# Edubot_v1_2.net
KiCad netlist of a schematic drawn in Altium Designer
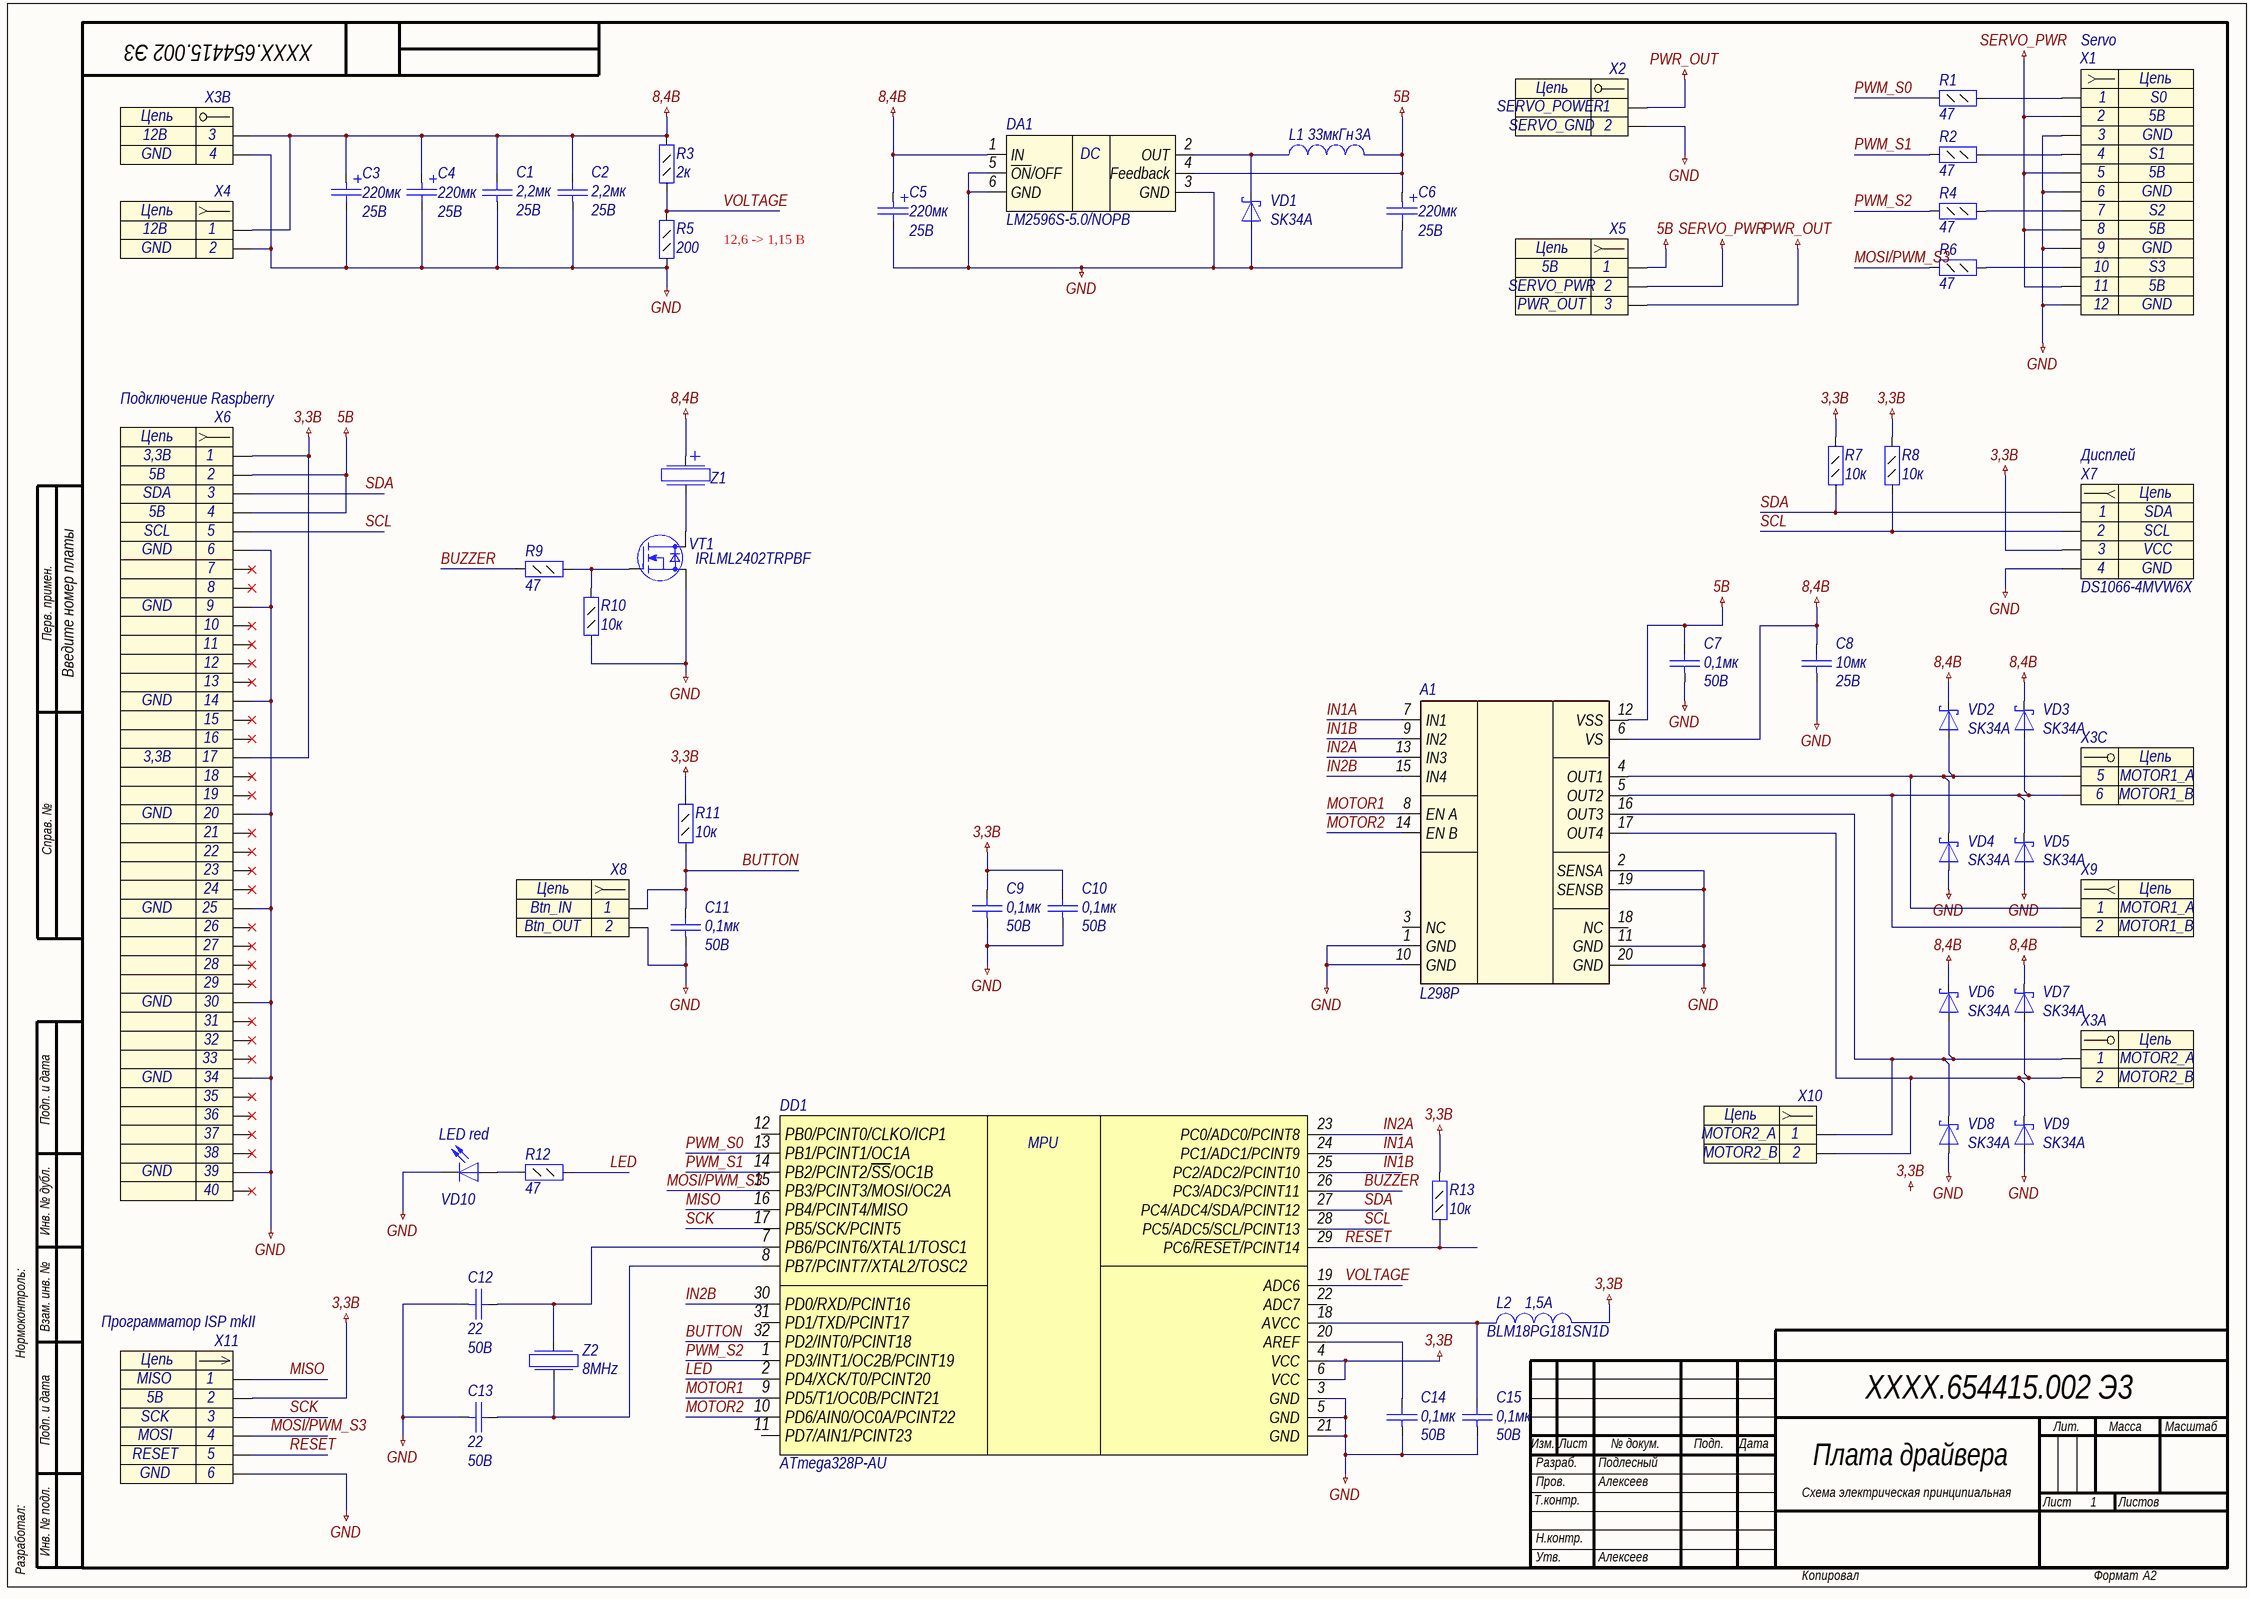
[diagram p0: Edubot v1.2.SchDoc]

(export (version "E")
  (design (tool "Eeschema 10.0.6"))
  (components
    (comp (ref "A1")
      (value "L298P")
      (footprint "POWERSO20")
      (description "FULL BRIDGE DC MOTOR DRIVER")
      (libsource (lib "MOP44") (part "L298P"))
    )
    (comp (ref "C1")
      (value "2,2мк")
      (footprint "C0805")
      (description "Конденсатор")
      (fields (field (name "VOLTAGE") "25B") (field (name "PART NUMBER") "GRM21BR71E225K"))
      (libsource (lib "MOP44") (part "Capacitor"))
    )
    (comp (ref "C2")
      (value "2,2мк")
      (footprint "C0805")
      (description "Конденсатор")
      (fields (field (name "VOLTAGE") "25B") (field (name "PART NUMBER") "GRM21BR71E225K"))
      (libsource (lib "MOP44") (part "Capacitor"))
    )
    (comp (ref "C3")
      (value "220мк")
      (footprint "Cap_SMD_radial_polar(8x10.2)")
      (description "Конденсатор полярный")
      (fields
        (field (name "VOLTAGE") "25В")
        (field (name "PART NUMBER") "JCK1E221M080105")
        (field (name "Comment") "Capacitor_pol")
      )
      (libsource (lib "MOP44") (part "Capacitor_pol"))
    )
    (comp (ref "C4")
      (value "220мк")
      (footprint "Cap_SMD_radial_polar(8x10.2)")
      (description "Конденсатор полярный")
      (fields
        (field (name "VOLTAGE") "25В")
        (field (name "PART NUMBER") "JCK1E221M080105")
        (field (name "Comment") "Capacitor_pol")
      )
      (libsource (lib "MOP44") (part "Capacitor_pol"))
    )
    (comp (ref "C5")
      (value "220мк")
      (footprint "Cap_SMD_radial_polar(8x10.2)")
      (description "Конденсатор полярный")
      (fields
        (field (name "VOLTAGE") "25В")
        (field (name "PART NUMBER") "JCK1E221M080105")
        (field (name "Comment") "Capacitor_pol")
      )
      (libsource (lib "MOP44") (part "Capacitor_pol"))
    )
    (comp (ref "C6")
      (value "220мк")
      (footprint "Cap_SMD_radial_polar(8x10.2)")
      (description "Конденсатор полярный")
      (fields
        (field (name "VOLTAGE") "25В")
        (field (name "PART NUMBER") "JCK1E221M080105")
        (field (name "Comment") "Capacitor_pol")
      )
      (libsource (lib "MOP44") (part "Capacitor_pol"))
    )
    (comp (ref "C7")
      (value "0,1мк")
      (footprint "C0805")
      (description "Конденсатор")
      (fields (field (name "VOLTAGE") "50В") (field (name "PART NUMBER") "GRM21BR71H104KA01L "))
      (libsource (lib "MOP44") (part "Capacitor"))
    )
    (comp (ref "C8")
      (value "10мк")
      (footprint "C1210")
      (description "Конденсатор")
      (fields (field (name "VOLTAGE") "25В") (field (name "PART NUMBER") "GRM32ER61A106K"))
      (libsource (lib "MOP44") (part "Capacitor"))
    )
    (comp (ref "C9")
      (value "0,1мк")
      (footprint "C0805")
      (description "Конденсатор")
      (fields (field (name "VOLTAGE") "50В") (field (name "PART NUMBER") "GRM21BR71H104KA01L "))
      (libsource (lib "MOP44") (part "Capacitor"))
    )
    (comp (ref "C10")
      (value "0,1мк")
      (footprint "C0805")
      (description "Конденсатор")
      (fields (field (name "VOLTAGE") "50В") (field (name "PART NUMBER") "GRM21BR71H104KA01L "))
      (libsource (lib "MOP44") (part "Capacitor"))
    )
    (comp (ref "C11")
      (value "0,1мк")
      (footprint "C0805")
      (description "Конденсатор")
      (fields (field (name "VOLTAGE") "50В") (field (name "PART NUMBER") "GRM21BR71H104KA01L "))
      (libsource (lib "MOP44") (part "Capacitor"))
    )
    (comp (ref "C12")
      (value "22")
      (footprint "C0805")
      (description "Конденсатор")
      (fields (field (name "VOLTAGE") "50В") (field (name "PART NUMBER") "MLCC22pFNPO50V5%0805"))
      (libsource (lib "MOP44") (part "Capacitor"))
    )
    (comp (ref "C13")
      (value "22")
      (footprint "C0805")
      (description "Конденсатор")
      (fields (field (name "VOLTAGE") "50В") (field (name "PART NUMBER") "MLCC22pFNPO50V5%0805"))
      (libsource (lib "MOP44") (part "Capacitor"))
    )
    (comp (ref "C14")
      (value "0,1мк")
      (footprint "C0805")
      (description "Конденсатор")
      (fields (field (name "VOLTAGE") "50В") (field (name "PART NUMBER") "GRM21BR71H104KA01L "))
      (libsource (lib "MOP44") (part "Capacitor"))
    )
    (comp (ref "C15")
      (value "0,1мк")
      (footprint "C0805")
      (description "Конденсатор")
      (fields (field (name "VOLTAGE") "50В") (field (name "PART NUMBER") "GRM21BR71H104KA01L "))
      (libsource (lib "MOP44") (part "Capacitor"))
    )
    (comp (ref "DA1")
      (value "LM2596S")
      (footprint "TO-263-5")
      (description "3-A Step-Down Voltage Regulator")
      (fields
        (field (name "PART NUMBER") "LM2596S-5.0/NOPB")
        (field (name "MANUFACTURER") "Texas Instruments")
      )
      (libsource (lib "MOP44") (part "LM2596S"))
    )
    (comp (ref "DD1")
      (value "ATmega328P-AU")
      (footprint "TQFP-32")
      (description "Микроконтроллер 8-Бит, picoPower, AVR, 20МГц, 32КБ Flash")
      (libsource (lib "MOP44") (part "ATmega328P-AU"))
    )
    (comp (ref "L1")
      (value "33мкГн")
      (footprint "IND_12.5x12.5")
      (description "EMI Suppression Filter")
      (fields
        (field (name "RATED CURRENT") "3A")
        (field (name "PART NUMBER") "B82477G4333M000")
        (field (name "Comment") "Inductor")
      )
      (libsource (lib "MOP44") (part "Inductor"))
    )
    (comp (ref "L2")
      (value "Inductor")
      (footprint "L0603")
      (description "EMI Suppression Filter")
      (fields (field (name "RATED CURRENT") "1,5A") (field (name "PART NUMBER") "BLM18PG181SN1D"))
      (libsource (lib "MOP44") (part "Inductor"))
    )
    (comp (ref "R1")
      (value "47")
      (footprint "R0805")
      (description "Резистор")
      (fields (field (name "PART NUMBER") "RC0805FR-0747RL") (field (name "POWER") "0,125Вт"))
      (libsource (lib "") (part "Resistor_0,125Вт_1"))
    )
    (comp (ref "R2")
      (value "47")
      (footprint "R0805")
      (description "Резистор")
      (fields (field (name "PART NUMBER") "RC0805FR-0747RL") (field (name "POWER") "0,125Вт"))
      (libsource (lib "") (part "Resistor_0,125Вт_1"))
    )
    (comp (ref "R3")
      (value "2к")
      (footprint "R0805")
      (description "Резистор")
      (fields (field (name "PART NUMBER") "RC0805FR-072KL") (field (name "POWER") "0,125Вт"))
      (libsource (lib "MOP44") (part "Resistor_0,125Вт"))
    )
    (comp (ref "R4")
      (value "47")
      (footprint "R0805")
      (description "Резистор")
      (fields (field (name "PART NUMBER") "RC0805FR-0747RL") (field (name "POWER") "0,125Вт"))
      (libsource (lib "") (part "Resistor_0,125Вт_1"))
    )
    (comp (ref "R5")
      (value "200")
      (footprint "R0805")
      (description "Резистор")
      (fields (field (name "PART NUMBER") "RC0805FR-07200RL") (field (name "POWER") "0,125Вт"))
      (libsource (lib "MOP44") (part "Resistor_0,125Вт"))
    )
    (comp (ref "R6")
      (value "47")
      (footprint "R0805")
      (description "Резистор")
      (fields (field (name "PART NUMBER") "RC0805FR-0747RL") (field (name "POWER") "0,125Вт"))
      (libsource (lib "") (part "Resistor_0,125Вт_1"))
    )
    (comp (ref "R7")
      (value "10к")
      (footprint "R0805")
      (description "Резистор")
      (fields (field (name "PART NUMBER") "RC0805FR-0710KL") (field (name "POWER") "0,125Вт"))
      (libsource (lib "MOP44") (part "Resistor_0,125Вт"))
    )
    (comp (ref "R8")
      (value "10к")
      (footprint "R0805")
      (description "Резистор")
      (fields (field (name "PART NUMBER") "RC0805FR-0710KL") (field (name "POWER") "0,125Вт"))
      (libsource (lib "MOP44") (part "Resistor_0,125Вт"))
    )
    (comp (ref "R9")
      (value "47")
      (footprint "R0805")
      (description "Резистор")
      (fields (field (name "PART NUMBER") "RC0805FR-0747RL") (field (name "POWER") "0,125Вт"))
      (libsource (lib "") (part "Resistor_0,125Вт_1"))
    )
    (comp (ref "R10")
      (value "10к")
      (footprint "R0805")
      (description "Резистор")
      (fields (field (name "PART NUMBER") "RC0805FR-0710KL") (field (name "POWER") "0,125Вт"))
      (libsource (lib "MOP44") (part "Resistor_0,125Вт"))
    )
    (comp (ref "R11")
      (value "10к")
      (footprint "R0805")
      (description "Резистор")
      (fields (field (name "PART NUMBER") "RC0805FR-0710KL") (field (name "POWER") "0,125Вт"))
      (libsource (lib "MOP44") (part "Resistor_0,125Вт"))
    )
    (comp (ref "R12")
      (value "47")
      (footprint "R0805")
      (description "Резистор")
      (fields (field (name "PART NUMBER") "RC0805FR-0747RL") (field (name "POWER") "0,125Вт"))
      (libsource (lib "") (part "Resistor_0,125Вт_1"))
    )
    (comp (ref "R13")
      (value "10к")
      (footprint "R0805")
      (description "Резистор")
      (fields (field (name "PART NUMBER") "RC0805FR-0710KL") (field (name "POWER") "0,125Вт"))
      (libsource (lib "MOP44") (part "Resistor_0,125Вт"))
    )
    (comp (ref "VD1")
      (value "DiodeSchottky")
      (footprint "SMA")
      (description "Диод Шоттки")
      (fields (field (name "PART NUMBER") "SK34A"))
      (libsource (lib "MOP44") (part "DiodeSchottky"))
    )
    (comp (ref "VD2")
      (value "DiodeSchottky")
      (footprint "SMA")
      (description "Диод Шоттки")
      (fields (field (name "PART NUMBER") "SK34A"))
      (libsource (lib "MOP44") (part "DiodeSchottky"))
    )
    (comp (ref "VD3")
      (value "DiodeSchottky")
      (footprint "SMA")
      (description "Диод Шоттки")
      (fields (field (name "PART NUMBER") "SK34A"))
      (libsource (lib "MOP44") (part "DiodeSchottky"))
    )
    (comp (ref "VD4")
      (value "DiodeSchottky")
      (footprint "SMA")
      (description "Диод Шоттки")
      (fields (field (name "PART NUMBER") "SK34A"))
      (libsource (lib "MOP44") (part "DiodeSchottky"))
    )
    (comp (ref "VD5")
      (value "DiodeSchottky")
      (footprint "SMA")
      (description "Диод Шоттки")
      (fields (field (name "PART NUMBER") "SK34A"))
      (libsource (lib "MOP44") (part "DiodeSchottky"))
    )
    (comp (ref "VD6")
      (value "DiodeSchottky")
      (footprint "SMA")
      (description "Диод Шоттки")
      (fields (field (name "PART NUMBER") "SK34A"))
      (libsource (lib "MOP44") (part "DiodeSchottky"))
    )
    (comp (ref "VD7")
      (value "DiodeSchottky")
      (footprint "SMA")
      (description "Диод Шоттки")
      (fields (field (name "PART NUMBER") "SK34A"))
      (libsource (lib "MOP44") (part "DiodeSchottky"))
    )
    (comp (ref "VD8")
      (value "DiodeSchottky")
      (footprint "SMA")
      (description "Диод Шоттки")
      (fields (field (name "PART NUMBER") "SK34A"))
      (libsource (lib "MOP44") (part "DiodeSchottky"))
    )
    (comp (ref "VD9")
      (value "DiodeSchottky")
      (footprint "SMA")
      (description "Диод Шоттки")
      (fields (field (name "PART NUMBER") "SK34A"))
      (libsource (lib "MOP44") (part "DiodeSchottky"))
    )
    (comp (ref "VD10")
      (value "LED")
      (footprint "L_0805")
      (description "Светодиод")
      (fields (field (name "PART NAME") "LED red") (field (name "PART NUMBER") "KP-2012EC"))
      (libsource (lib "MOP44") (part "LED"))
    )
    (comp (ref "VT1")
      (value "N-MOSFET")
      (footprint "SOT23-3")
      (fields
        (field (name "PART NUMBER") "IRLML2402TRPBF")
        (field (name "MANUFACTURER") "International Rectifier")
      )
      (libsource (lib "MOP44") (part "N-MOSFET"))
    )
    (comp (ref "X1")
      (value "Servo")
      (footprint "PLS-12")
      (description "Разъем - 12 конт. розетка")
      (libsource (lib "MOP44") (part "Header_12_sct"))
    )
    (comp (ref "X2")
      (value "Header_2_trm")
      (footprint "TERMINAL-2WAY-3.5MM")
      (description "Разъем - 2 конт. клеммник")
      (libsource (lib "MOP44") (part "Header_2_trm"))
    )
    (comp (ref "X3")
      (value "~")
      (footprint "TERMINAL-6WAY-5MM")
      (description "POWER")
      (libsource (lib "MOP44") (part "Header_6_motor"))
    )
    (comp (ref "X4")
      (value "Header_2_sct")
      (footprint "2HOLE_2.5")
      (description "Разъем - 2 конт. розетка")
      (libsource (lib "MOP44") (part "Header_2_sct"))
    )
    (comp (ref "X5")
      (value "Header_3_sct")
      (footprint "TAB_3PAD")
      (description "Разъем - 3 конт. розетка")
      (libsource (lib "MOP44") (part "Header_3_sct"))
    )
    (comp (ref "X6")
      (value "Подключение Raspberry")
      (footprint "PBS-40")
      (description "Разъем - 5 конт. розетка")
      (libsource (lib "MOP44") (part "Header_40_sct"))
    )
    (comp (ref "X7")
      (value "Дисплей")
      (footprint "MW-4M")
      (description "Разъем - 4 конт. розетка")
      (fields (field (name "PART NUMBER") "DS1066-4MVW6X"))
      (libsource (lib "MOP44") (part "Header_4_sct"))
    )
    (comp (ref "X8")
      (value "Header_2_sct")
      (footprint "2HOLE_2.5")
      (description "Разъем - 2 конт. розетка")
      (libsource (lib "MOP44") (part "Header_2_sct"))
    )
    (comp (ref "X9")
      (value "Header_2_sct")
      (footprint "2HOLE_2.5")
      (description "Разъем - 2 конт. розетка")
      (libsource (lib "") (part "Header_2_sct_1"))
    )
    (comp (ref "X10")
      (value "Header_2_sct")
      (footprint "2HOLE_2.5")
      (description "Разъем - 2 конт. розетка")
      (libsource (lib "MOP44") (part "Header_2_sct"))
    )
    (comp (ref "X11")
      (value "Программатор ISP mkII")
      (footprint "PLS2-6")
      (description "Разъем - 6 конт. вилка")
      (libsource (lib "MOP44") (part "ISP MKII"))
    )
    (comp (ref "Z1")
      (value "~")
      (footprint "Buzzer_gen_12mm")
      (description "Пьезоизлучатель звуковой без генератора")
      (fields (field (name "PART NUMBER") "HCM1212X"))
      (libsource (lib "MOP44") (part "Buzzer"))
    )
    (comp (ref "Z2")
      (value "Crystal")
      (footprint "QSMD5.0x3.2x1.0")
      (description "Кварцевый резонатор")
      (fields (field (name "FREQUENCE") "8MHz") (field (name "PART NUMBER") "KX-9A"))
      (libsource (lib "MOP44") (part "Crystal"))
    )
  )
  (nets
    (net (code "1") (name "/BUTTON") (class "Default")
      (node (ref "C11") (pin "2") (pinfunction "2_2") (pintype "passive"))
      (node (ref "DD1") (pin "32") (pinfunction "PD2/INT0/PCINT18_32") (pintype "passive"))
      (node (ref "R11") (pin "1") (pinfunction "1_1") (pintype "passive"))
      (node (ref "X8") (pin "1") (pinfunction "1_1") (pintype "passive"))
    )
    (net (code "2") (name "/BUZZER") (class "Default")
      (node (ref "DD1") (pin "26") (pinfunction "PC3/ADC3/PCINT11_26") (pintype "passive"))
      (node (ref "R9") (pin "1") (pinfunction "1_1") (pintype "passive"))
    )
    (net (code "3") (name "/IN1A") (class "Default")
      (node (ref "A1") (pin "7") (pinfunction "IN1_7") (pintype "passive"))
      (node (ref "DD1") (pin "24") (pinfunction "PC1/ADC1/PCINT9_24") (pintype "passive"))
    )
    (net (code "4") (name "/IN1B") (class "Default")
      (node (ref "A1") (pin "9") (pinfunction "IN2_9") (pintype "passive"))
      (node (ref "DD1") (pin "25") (pinfunction "PC2/ADC2/PCINT10_25") (pintype "passive"))
    )
    (net (code "5") (name "/IN2A") (class "Default")
      (node (ref "A1") (pin "13") (pinfunction "IN3_13") (pintype "passive"))
      (node (ref "DD1") (pin "23") (pinfunction "PC0/ADC0/PCINT8_23") (pintype "passive"))
    )
    (net (code "6") (name "/IN2B") (class "Default")
      (node (ref "A1") (pin "15") (pinfunction "IN4_15") (pintype "passive"))
      (node (ref "DD1") (pin "30") (pinfunction "PD0/RXD/PCINT16_30") (pintype "passive"))
    )
    (net (code "7") (name "/LED") (class "Default")
      (node (ref "DD1") (pin "2") (pinfunction "PD4/XCK/T0/PCINT20_2") (pintype "passive"))
      (node (ref "R12") (pin "2") (pinfunction "2_2") (pintype "passive"))
    )
    (net (code "8") (name "/MISO") (class "Default")
      (node (ref "DD1") (pin "16") (pinfunction "PB4/PCINT4/MISO_16") (pintype "passive"))
      (node (ref "X11") (pin "1") (pinfunction "1_1") (pintype "passive"))
    )
    (net (code "9") (name "/MOSI{slash}PWM_S3") (class "Default")
      (node (ref "DD1") (pin "15") (pinfunction "PB3/PCINT3/MOSI/OC2A_15") (pintype "passive"))
      (node (ref "R6") (pin "1") (pinfunction "1_1") (pintype "passive"))
      (node (ref "X11") (pin "4") (pinfunction "4_4") (pintype "passive"))
    )
    (net (code "10") (name "/MOTOR1") (class "Default")
      (node (ref "A1") (pin "8") (pinfunction "EN_A_8") (pintype "passive"))
      (node (ref "DD1") (pin "9") (pinfunction "PD5/T1/OC0B/PCINT21_9") (pintype "passive"))
    )
    (net (code "11") (name "/MOTOR2") (class "Default")
      (node (ref "A1") (pin "14") (pinfunction "EN_B_14") (pintype "passive"))
      (node (ref "DD1") (pin "10") (pinfunction "PD6/AIN0/OC0A/PCINT22_10") (pintype "passive"))
    )
    (net (code "12") (name "/PWM_S0") (class "Default")
      (node (ref "DD1") (pin "13") (pinfunction "PB1/PCINT1/OC1A_13") (pintype "passive"))
      (node (ref "R1") (pin "1") (pinfunction "1_1") (pintype "passive"))
    )
    (net (code "13") (name "/PWM_S1") (class "Default")
      (node (ref "DD1") (pin "14") (pinfunction "PB2/PCINT2/~{SS}/OC1B_14") (pintype "passive"))
      (node (ref "R2") (pin "1") (pinfunction "1_1") (pintype "passive"))
    )
    (net (code "14") (name "/PWM_S2") (class "Default")
      (node (ref "DD1") (pin "1") (pinfunction "PD3/INT1/OC2B/PCINT19_1") (pintype "passive"))
      (node (ref "R4") (pin "1") (pinfunction "1_1") (pintype "passive"))
    )
    (net (code "15") (name "/RESET") (class "Default")
      (node (ref "DD1") (pin "29") (pinfunction "PC6/~{RESET}/PCINT14_29") (pintype "passive"))
      (node (ref "R13") (pin "1") (pinfunction "1_1") (pintype "passive"))
      (node (ref "X11") (pin "5") (pinfunction "5_5") (pintype "passive"))
    )
    (net (code "16") (name "/SCK") (class "Default")
      (node (ref "DD1") (pin "17") (pinfunction "PB5/SCK/PCINT5_17") (pintype "passive"))
      (node (ref "X11") (pin "3") (pinfunction "3_3") (pintype "passive"))
    )
    (net (code "17") (name "/SCL") (class "Default")
      (node (ref "DD1") (pin "28") (pinfunction "PC5/ADC5/SCL/PCINT13_28") (pintype "passive"))
      (node (ref "R8") (pin "1") (pinfunction "1_1") (pintype "passive"))
      (node (ref "X6") (pin "5") (pinfunction "5_5") (pintype "passive"))
      (node (ref "X7") (pin "2") (pinfunction "2_2") (pintype "passive"))
    )
    (net (code "18") (name "/SDA") (class "Default")
      (node (ref "DD1") (pin "27") (pinfunction "PC4/ADC4/SDA/PCINT12_27") (pintype "passive"))
      (node (ref "R7") (pin "1") (pinfunction "1_1") (pintype "passive"))
      (node (ref "X6") (pin "3") (pinfunction "3_3") (pintype "passive"))
      (node (ref "X7") (pin "1") (pinfunction "1_1") (pintype "passive"))
    )
    (net (code "19") (name "/VOLTAGE") (class "Default")
      (node (ref "DD1") (pin "19") (pinfunction "ADC6_19") (pintype "passive"))
      (node (ref "R3") (pin "1") (pinfunction "1_1") (pintype "passive"))
      (node (ref "R5") (pin "2") (pinfunction "2_2") (pintype "passive"))
    )
    (net (code "20") (name "3,3B") (class "Default")
      (node (ref "C10") (pin "2") (pinfunction "2_2") (pintype "passive"))
      (node (ref "C9") (pin "2") (pinfunction "2_2") (pintype "passive"))
      (node (ref "DD1") (pin "4") (pinfunction "VCC_4") (pintype "passive"))
      (node (ref "DD1") (pin "6") (pinfunction "VCC_6") (pintype "passive"))
      (node (ref "L2") (pin "2") (pinfunction "2_2") (pintype "passive"))
      (node (ref "R11") (pin "2") (pinfunction "2_2") (pintype "passive"))
      (node (ref "R13") (pin "2") (pinfunction "2_2") (pintype "passive"))
      (node (ref "R7") (pin "2") (pinfunction "2_2") (pintype "passive"))
      (node (ref "R8") (pin "2") (pinfunction "2_2") (pintype "passive"))
      (node (ref "X11") (pin "2") (pinfunction "2_2") (pintype "passive"))
      (node (ref "X6") (pin "1") (pinfunction "1_1") (pintype "passive"))
      (node (ref "X6") (pin "17") (pinfunction "17_17") (pintype "passive"))
      (node (ref "X7") (pin "3") (pinfunction "3_3") (pintype "passive"))
    )
    (net (code "21") (name "5В") (class "Default")
      (node (ref "A1") (pin "12") (pinfunction "VSS_12") (pintype "passive"))
      (node (ref "C6") (pin "1") (pinfunction "1_1") (pintype "passive"))
      (node (ref "C7") (pin "2") (pinfunction "2_2") (pintype "passive"))
      (node (ref "DA1") (pin "4") (pinfunction "Feedback_4") (pintype "power_in"))
      (node (ref "L1") (pin "2") (pinfunction "2_2") (pintype "passive"))
      (node (ref "X5") (pin "1") (pinfunction "1_1") (pintype "passive"))
      (node (ref "X6") (pin "2") (pinfunction "2_2") (pintype "passive"))
      (node (ref "X6") (pin "4") (pinfunction "4_4") (pintype "passive"))
    )
    (net (code "22") (name "8,4В") (class "Default")
      (node (ref "A1") (pin "6") (pinfunction "VS_6") (pintype "passive"))
      (node (ref "C1") (pin "2") (pinfunction "2_2") (pintype "passive"))
      (node (ref "C2") (pin "2") (pinfunction "2_2") (pintype "passive"))
      (node (ref "C3") (pin "1") (pinfunction "1_1") (pintype "passive"))
      (node (ref "C4") (pin "1") (pinfunction "1_1") (pintype "passive"))
      (node (ref "C5") (pin "1") (pinfunction "1_1") (pintype "passive"))
      (node (ref "C8") (pin "2") (pinfunction "2_2") (pintype "passive"))
      (node (ref "DA1") (pin "1") (pinfunction "IN_1") (pintype "power_in"))
      (node (ref "R3") (pin "2") (pinfunction "2_2") (pintype "passive"))
      (node (ref "VD2") (pin "1") (pinfunction "K_1") (pintype "passive"))
      (node (ref "VD3") (pin "1") (pinfunction "K_1") (pintype "passive"))
      (node (ref "VD6") (pin "1") (pinfunction "K_1") (pintype "passive"))
      (node (ref "VD7") (pin "1") (pinfunction "K_1") (pintype "passive"))
      (node (ref "X3") (pin "3") (pinfunction "3_3") (pintype "passive"))
      (node (ref "X4") (pin "1") (pinfunction "1_1") (pintype "passive"))
      (node (ref "Z1") (pin "1") (pinfunction "1_1") (pintype "passive"))
    )
    (net (code "23") (name "GND") (class "Default")
      (node (ref "A1") (pin "1") (pinfunction "GND_1") (pintype "passive"))
      (node (ref "A1") (pin "10") (pinfunction "GND_10") (pintype "passive"))
      (node (ref "A1") (pin "11") (pinfunction "GND_11") (pintype "passive"))
      (node (ref "A1") (pin "19") (pinfunction "SENSB_19") (pintype "passive"))
      (node (ref "A1") (pin "2") (pinfunction "SENSA_2") (pintype "passive"))
      (node (ref "A1") (pin "20") (pinfunction "GND_20") (pintype "passive"))
      (node (ref "C1") (pin "1") (pinfunction "1_1") (pintype "passive"))
      (node (ref "C10") (pin "1") (pinfunction "1_1") (pintype "passive"))
      (node (ref "C11") (pin "1") (pinfunction "1_1") (pintype "passive"))
      (node (ref "C12") (pin "1") (pinfunction "1_1") (pintype "passive"))
      (node (ref "C13") (pin "1") (pinfunction "1_1") (pintype "passive"))
      (node (ref "C14") (pin "1") (pinfunction "1_1") (pintype "passive"))
      (node (ref "C15") (pin "1") (pinfunction "1_1") (pintype "passive"))
      (node (ref "C2") (pin "1") (pinfunction "1_1") (pintype "passive"))
      (node (ref "C3") (pin "2") (pinfunction "2_2") (pintype "passive"))
      (node (ref "C4") (pin "2") (pinfunction "2_2") (pintype "passive"))
      (node (ref "C5") (pin "2") (pinfunction "2_2") (pintype "passive"))
      (node (ref "C6") (pin "2") (pinfunction "2_2") (pintype "passive"))
      (node (ref "C7") (pin "1") (pinfunction "1_1") (pintype "passive"))
      (node (ref "C8") (pin "1") (pinfunction "1_1") (pintype "passive"))
      (node (ref "C9") (pin "1") (pinfunction "1_1") (pintype "passive"))
      (node (ref "DA1") (pin "3") (pinfunction "GND_3") (pintype "power_in"))
      (node (ref "DA1") (pin "5") (pinfunction "~{ON}/OFF_5") (pintype "power_in"))
      (node (ref "DA1") (pin "6") (pinfunction "GND_6") (pintype "power_in"))
      (node (ref "DD1") (pin "21") (pinfunction "GND_21") (pintype "passive"))
      (node (ref "DD1") (pin "3") (pinfunction "GND_3") (pintype "passive"))
      (node (ref "DD1") (pin "5") (pinfunction "GND_5") (pintype "passive"))
      (node (ref "R10") (pin "1") (pinfunction "1_1") (pintype "passive"))
      (node (ref "R5") (pin "1") (pinfunction "1_1") (pintype "passive"))
      (node (ref "VD1") (pin "2") (pinfunction "A_2") (pintype "passive"))
      (node (ref "VD10") (pin "1") (pinfunction "K_1") (pintype "passive"))
      (node (ref "VD4") (pin "2") (pinfunction "A_2") (pintype "passive"))
      (node (ref "VD5") (pin "2") (pinfunction "A_2") (pintype "passive"))
      (node (ref "VD8") (pin "2") (pinfunction "A_2") (pintype "passive"))
      (node (ref "VD9") (pin "2") (pinfunction "A_2") (pintype "passive"))
      (node (ref "VT1") (pin "2") (pinfunction "S_2") (pintype "passive"))
      (node (ref "X1") (pin "12") (pinfunction "12_12") (pintype "passive"))
      (node (ref "X1") (pin "3") (pinfunction "3_3") (pintype "passive"))
      (node (ref "X1") (pin "6") (pinfunction "6_6") (pintype "passive"))
      (node (ref "X1") (pin "9") (pinfunction "9_9") (pintype "passive"))
      (node (ref "X11") (pin "6") (pinfunction "6_6") (pintype "passive"))
      (node (ref "X2") (pin "2") (pinfunction "2_2") (pintype "passive"))
      (node (ref "X3") (pin "4") (pinfunction "4_4") (pintype "passive"))
      (node (ref "X4") (pin "2") (pinfunction "2_2") (pintype "passive"))
      (node (ref "X6") (pin "14") (pinfunction "14_14") (pintype "passive"))
      (node (ref "X6") (pin "20") (pinfunction "20_20") (pintype "passive"))
      (node (ref "X6") (pin "25") (pinfunction "25_25") (pintype "passive"))
      (node (ref "X6") (pin "30") (pinfunction "30_30") (pintype "passive"))
      (node (ref "X6") (pin "34") (pinfunction "34_34") (pintype "passive"))
      (node (ref "X6") (pin "39") (pinfunction "39_39") (pintype "passive"))
      (node (ref "X6") (pin "6") (pinfunction "6_6") (pintype "passive"))
      (node (ref "X6") (pin "9") (pinfunction "9_9") (pintype "passive"))
      (node (ref "X7") (pin "4") (pinfunction "4_4") (pintype "passive"))
      (node (ref "X8") (pin "2") (pinfunction "2_2") (pintype "passive"))
    )
    (net (code "24") (name "Net-(A1-OUT1)") (class "Default")
      (node (ref "A1") (pin "4") (pinfunction "OUT1_4") (pintype "passive"))
      (node (ref "VD2") (pin "2") (pinfunction "A_2") (pintype "passive"))
      (node (ref "VD4") (pin "1") (pinfunction "K_1") (pintype "passive"))
      (node (ref "X3") (pin "5") (pinfunction "5_5") (pintype "passive"))
      (node (ref "X9") (pin "1") (pinfunction "1_1") (pintype "passive"))
    )
    (net (code "25") (name "Net-(A1-OUT2)") (class "Default")
      (node (ref "A1") (pin "5") (pinfunction "OUT2_5") (pintype "passive"))
      (node (ref "VD3") (pin "2") (pinfunction "A_2") (pintype "passive"))
      (node (ref "VD5") (pin "1") (pinfunction "K_1") (pintype "passive"))
      (node (ref "X3") (pin "6") (pinfunction "6_6") (pintype "passive"))
      (node (ref "X9") (pin "2") (pinfunction "2_2") (pintype "passive"))
    )
    (net (code "26") (name "Net-(A1-OUT3)") (class "Default")
      (node (ref "A1") (pin "16") (pinfunction "OUT3_16") (pintype "passive"))
      (node (ref "VD6") (pin "2") (pinfunction "A_2") (pintype "passive"))
      (node (ref "VD8") (pin "1") (pinfunction "K_1") (pintype "passive"))
      (node (ref "X10") (pin "1") (pinfunction "1_1") (pintype "passive"))
      (node (ref "X3") (pin "1") (pinfunction "1_1") (pintype "passive"))
    )
    (net (code "27") (name "Net-(A1-OUT4)") (class "Default")
      (node (ref "A1") (pin "17") (pinfunction "OUT4_17") (pintype "passive"))
      (node (ref "VD7") (pin "2") (pinfunction "A_2") (pintype "passive"))
      (node (ref "VD9") (pin "1") (pinfunction "K_1") (pintype "passive"))
      (node (ref "X10") (pin "2") (pinfunction "2_2") (pintype "passive"))
      (node (ref "X3") (pin "2") (pinfunction "2_2") (pintype "passive"))
    )
    (net (code "28") (name "Net-(DA1-OUT)") (class "Default")
      (node (ref "DA1") (pin "2") (pinfunction "OUT_2") (pintype "power_in"))
      (node (ref "L1") (pin "1") (pinfunction "1_1") (pintype "passive"))
      (node (ref "VD1") (pin "1") (pinfunction "K_1") (pintype "passive"))
    )
    (net (code "29") (name "Net-(DD1-AREF)") (class "Default")
      (node (ref "C14") (pin "2") (pinfunction "2_2") (pintype "passive"))
      (node (ref "DD1") (pin "20") (pinfunction "AREF_20") (pintype "passive"))
    )
    (net (code "30") (name "Net-(DD1-AVCC)") (class "Default")
      (node (ref "C15") (pin "2") (pinfunction "2_2") (pintype "passive"))
      (node (ref "DD1") (pin "18") (pinfunction "AVCC_18") (pintype "passive"))
      (node (ref "L2") (pin "1") (pinfunction "1_1") (pintype "passive"))
    )
    (net (code "31") (name "Net-(DD1-PB6{slash}PCINT6{slash}XTAL1{slash}TOSC1)") (class "Default")
      (node (ref "C12") (pin "2") (pinfunction "2_2") (pintype "passive"))
      (node (ref "DD1") (pin "7") (pinfunction "PB6/PCINT6/XTAL1/TOSC1_7") (pintype "passive"))
      (node (ref "Z2") (pin "2") (pinfunction "2_2") (pintype "passive"))
    )
    (net (code "32") (name "Net-(DD1-PB7{slash}PCINT7{slash}XTAL2{slash}TOSC2)") (class "Default")
      (node (ref "C13") (pin "2") (pinfunction "2_2") (pintype "passive"))
      (node (ref "DD1") (pin "8") (pinfunction "PB7/PCINT7/XTAL2/TOSC2_8") (pintype "passive"))
      (node (ref "Z2") (pin "1") (pinfunction "1_1") (pintype "passive"))
    )
    (net (code "33") (name "Net-(R1-Pad2)") (class "Default")
      (node (ref "R1") (pin "2") (pinfunction "2_2") (pintype "passive"))
      (node (ref "X1") (pin "1") (pinfunction "1_1") (pintype "passive"))
    )
    (net (code "34") (name "Net-(R2-Pad2)") (class "Default")
      (node (ref "R2") (pin "2") (pinfunction "2_2") (pintype "passive"))
      (node (ref "X1") (pin "4") (pinfunction "4_4") (pintype "passive"))
    )
    (net (code "35") (name "Net-(R4-Pad2)") (class "Default")
      (node (ref "R4") (pin "2") (pinfunction "2_2") (pintype "passive"))
      (node (ref "X1") (pin "7") (pinfunction "7_7") (pintype "passive"))
    )
    (net (code "36") (name "Net-(R6-Pad2)") (class "Default")
      (node (ref "R6") (pin "2") (pinfunction "2_2") (pintype "passive"))
      (node (ref "X1") (pin "10") (pinfunction "10_10") (pintype "passive"))
    )
    (net (code "37") (name "Net-(VD10-A)") (class "Default")
      (node (ref "R12") (pin "1") (pinfunction "1_1") (pintype "passive"))
      (node (ref "VD10") (pin "2") (pinfunction "A_2") (pintype "passive"))
    )
    (net (code "38") (name "Net-(VT1-D)") (class "Default")
      (node (ref "VT1") (pin "3") (pinfunction "D_3") (pintype "passive"))
      (node (ref "Z1") (pin "2") (pinfunction "2_2") (pintype "passive"))
    )
    (net (code "39") (name "Net-(VT1-G)") (class "Default")
      (node (ref "R10") (pin "2") (pinfunction "2_2") (pintype "passive"))
      (node (ref "R9") (pin "2") (pinfunction "2_2") (pintype "passive"))
      (node (ref "VT1") (pin "1") (pinfunction "G_1") (pintype "passive"))
    )
    (net (code "40") (name "PWR_OUT") (class "Default")
      (node (ref "X2") (pin "1") (pinfunction "1_1") (pintype "passive"))
      (node (ref "X5") (pin "3") (pinfunction "3_3") (pintype "passive"))
    )
    (net (code "41") (name "SERVO_PWR") (class "Default")
      (node (ref "X1") (pin "11") (pinfunction "11_11") (pintype "passive"))
      (node (ref "X1") (pin "2") (pinfunction "2_2") (pintype "passive"))
      (node (ref "X1") (pin "5") (pinfunction "5_5") (pintype "passive"))
      (node (ref "X1") (pin "8") (pinfunction "8_8") (pintype "passive"))
      (node (ref "X5") (pin "2") (pinfunction "2_2") (pintype "passive"))
    )
    (net (code "42") (name "unconnected-(A1-NC-Pad3)") (class "Default")
      (node (ref "A1") (pin "3") (pinfunction "NC_3") (pintype "passive"))
    )
    (net (code "43") (name "unconnected-(A1-NC-Pad18)") (class "Default")
      (node (ref "A1") (pin "18") (pinfunction "NC_18") (pintype "passive"))
    )
    (net (code "44") (name "unconnected-(DD1-ADC7-Pad22)") (class "Default")
      (node (ref "DD1") (pin "22") (pinfunction "ADC7_22") (pintype "passive"))
    )
    (net (code "45") (name "unconnected-(DD1-PB0{slash}PCINT0{slash}CLKO{slash}ICP1-Pad12)") (class "Default")
      (node (ref "DD1") (pin "12") (pinfunction "PB0/PCINT0/CLKO/ICP1_12") (pintype "passive"))
    )
    (net (code "46") (name "unconnected-(DD1-PD1{slash}TXD{slash}PCINT17-Pad31)") (class "Default")
      (node (ref "DD1") (pin "31") (pinfunction "PD1/TXD/PCINT17_31") (pintype "passive"))
    )
    (net (code "47") (name "unconnected-(DD1-PD7{slash}AIN1{slash}PCINT23-Pad11)") (class "Default")
      (node (ref "DD1") (pin "11") (pinfunction "PD7/AIN1/PCINT23_11") (pintype "passive"))
    )
    (net (code "48") (name "unconnected-(X6-Pad7)") (class "Default")
      (node (ref "X6") (pin "7") (pinfunction "7_7") (pintype "passive+no_connect"))
    )
    (net (code "49") (name "unconnected-(X6-Pad8)") (class "Default")
      (node (ref "X6") (pin "8") (pinfunction "8_8") (pintype "passive+no_connect"))
    )
    (net (code "50") (name "unconnected-(X6-Pad10)") (class "Default")
      (node (ref "X6") (pin "10") (pinfunction "10_10") (pintype "passive+no_connect"))
    )
    (net (code "51") (name "unconnected-(X6-Pad11)") (class "Default")
      (node (ref "X6") (pin "11") (pinfunction "11_11") (pintype "passive+no_connect"))
    )
    (net (code "52") (name "unconnected-(X6-Pad12)") (class "Default")
      (node (ref "X6") (pin "12") (pinfunction "12_12") (pintype "passive+no_connect"))
    )
    (net (code "53") (name "unconnected-(X6-Pad13)") (class "Default")
      (node (ref "X6") (pin "13") (pinfunction "13_13") (pintype "passive+no_connect"))
    )
    (net (code "54") (name "unconnected-(X6-Pad15)") (class "Default")
      (node (ref "X6") (pin "15") (pinfunction "15_15") (pintype "passive+no_connect"))
    )
    (net (code "55") (name "unconnected-(X6-Pad16)") (class "Default")
      (node (ref "X6") (pin "16") (pinfunction "16_16") (pintype "passive+no_connect"))
    )
    (net (code "56") (name "unconnected-(X6-Pad18)") (class "Default")
      (node (ref "X6") (pin "18") (pinfunction "18_18") (pintype "passive+no_connect"))
    )
    (net (code "57") (name "unconnected-(X6-Pad19)") (class "Default")
      (node (ref "X6") (pin "19") (pinfunction "19_19") (pintype "passive+no_connect"))
    )
    (net (code "58") (name "unconnected-(X6-Pad21)") (class "Default")
      (node (ref "X6") (pin "21") (pinfunction "21_21") (pintype "passive+no_connect"))
    )
    (net (code "59") (name "unconnected-(X6-Pad22)") (class "Default")
      (node (ref "X6") (pin "22") (pinfunction "22_22") (pintype "passive+no_connect"))
    )
    (net (code "60") (name "unconnected-(X6-Pad23)") (class "Default")
      (node (ref "X6") (pin "23") (pinfunction "23_23") (pintype "passive+no_connect"))
    )
    (net (code "61") (name "unconnected-(X6-Pad24)") (class "Default")
      (node (ref "X6") (pin "24") (pinfunction "24_24") (pintype "passive+no_connect"))
    )
    (net (code "62") (name "unconnected-(X6-Pad26)") (class "Default")
      (node (ref "X6") (pin "26") (pinfunction "26_26") (pintype "passive+no_connect"))
    )
    (net (code "63") (name "unconnected-(X6-Pad27)") (class "Default")
      (node (ref "X6") (pin "27") (pinfunction "27_27") (pintype "passive+no_connect"))
    )
    (net (code "64") (name "unconnected-(X6-Pad28)") (class "Default")
      (node (ref "X6") (pin "28") (pinfunction "28_28") (pintype "passive+no_connect"))
    )
    (net (code "65") (name "unconnected-(X6-Pad29)") (class "Default")
      (node (ref "X6") (pin "29") (pinfunction "29_29") (pintype "passive+no_connect"))
    )
    (net (code "66") (name "unconnected-(X6-Pad31)") (class "Default")
      (node (ref "X6") (pin "31") (pinfunction "31_31") (pintype "passive+no_connect"))
    )
    (net (code "67") (name "unconnected-(X6-Pad32)") (class "Default")
      (node (ref "X6") (pin "32") (pinfunction "32_32") (pintype "passive+no_connect"))
    )
    (net (code "68") (name "unconnected-(X6-Pad33)") (class "Default")
      (node (ref "X6") (pin "33") (pinfunction "33_33") (pintype "passive+no_connect"))
    )
    (net (code "69") (name "unconnected-(X6-Pad35)") (class "Default")
      (node (ref "X6") (pin "35") (pinfunction "35_35") (pintype "passive+no_connect"))
    )
    (net (code "70") (name "unconnected-(X6-Pad36)") (class "Default")
      (node (ref "X6") (pin "36") (pinfunction "36_36") (pintype "passive+no_connect"))
    )
    (net (code "71") (name "unconnected-(X6-Pad37)") (class "Default")
      (node (ref "X6") (pin "37") (pinfunction "37_37") (pintype "passive+no_connect"))
    )
    (net (code "72") (name "unconnected-(X6-Pad38)") (class "Default")
      (node (ref "X6") (pin "38") (pinfunction "38_38") (pintype "passive+no_connect"))
    )
    (net (code "73") (name "unconnected-(X6-Pad40)") (class "Default")
      (node (ref "X6") (pin "40") (pinfunction "40_40") (pintype "passive+no_connect"))
    )
  )
)
